# TransmisorVideo5_8GHz.net
KiCad netlist of a schematic drawn in Altium Designer
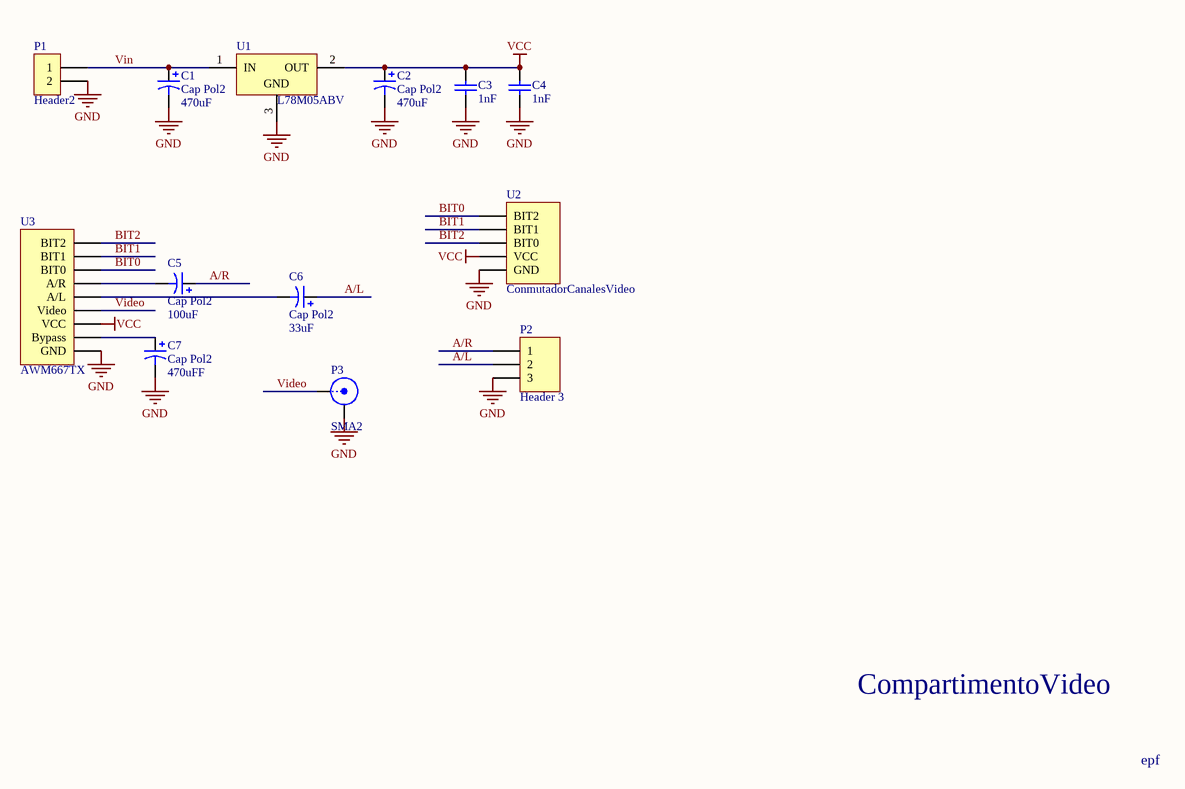
[diagram p0: TransmisorVideo5_8GHz.SchDoc]

(export (version "E")
  (design (tool "Eeschema 10.0.6"))
  (components
    (comp (ref "C1")
      (value "Cap Pol2")
      (footprint "TC7360-2924")
      (description "Polarized Capacitor (Axial)")
      (fields (field (name "ALTIUM_VALUE") "470uF") (field (name "PUBLISHER") "Altium Limited"))
      (libsource (lib "epf") (part "Cap Pol2"))
    )
    (comp (ref "C2")
      (value "Cap Pol2")
      (footprint "TC7360-2924")
      (description "Polarized Capacitor (Axial)")
      (fields (field (name "ALTIUM_VALUE") "470uF") (field (name "PUBLISHER") "Altium Limited"))
      (libsource (lib "epf") (part "Cap Pol2"))
    )
    (comp (ref "C3")
      (value "1nF")
      (footprint "0805_CAP")
      (fields (field (name "Comment") "Capacitor"))
      (libsource (lib "epf") (part "Cap"))
    )
    (comp (ref "C4")
      (value "1nF")
      (footprint "0805_CAP")
      (fields (field (name "Comment") "Capacitor"))
      (libsource (lib "epf") (part "Cap"))
    )
    (comp (ref "C5")
      (value "Cap Pol2")
      (footprint "TC7360-2924")
      (description "Polarized Capacitor (Axial)")
      (fields (field (name "ALTIUM_VALUE") "100uF") (field (name "PUBLISHER") "Altium Limited"))
      (libsource (lib "epf") (part "Cap Pol2"))
    )
    (comp (ref "C6")
      (value "Cap Pol2")
      (footprint "TC7360-2924")
      (description "Polarized Capacitor (Axial)")
      (fields (field (name "ALTIUM_VALUE") "33uF") (field (name "PUBLISHER") "Altium Limited"))
      (libsource (lib "epf") (part "Cap Pol2"))
    )
    (comp (ref "C7")
      (value "Cap Pol2")
      (footprint "TC7360-2924")
      (description "Polarized Capacitor (Axial)")
      (fields (field (name "ALTIUM_VALUE") "470uFF") (field (name "PUBLISHER") "Altium Limited"))
      (libsource (lib "epf") (part "Cap Pol2"))
    )
    (comp (ref "P1") (value "Header2") (footprint "Header2Macho") (libsource (lib "epf") (part "Header2")))
    (comp (ref "P2")
      (value "Header 3")
      (footprint "HDR1X3")
      (description "Header, 3-Pin")
      (fields (field (name "PUBLISHER") "Altium Limited"))
      (libsource (lib "Miscellaneous Connectors") (part "Header 3"))
    )
    (comp (ref "P3")
      (value "SMA2")
      (footprint "SMA-4HOLE")
      (description "BNC Elbow Connector")
      (fields (field (name "PUBLISHER") "Altium Limited"))
      (libsource (lib "epf") (part "SMA2"))
    )
    (comp (ref "U1")
      (value "L78M05ABV")
      (footprint "TO220V")
      (description "Precision 500mA Regulator")
      (fields (field (name "PUBLISHER") "Altium Limited"))
      (libsource (lib "epf") (part "L78M05ABV"))
    )
    (comp (ref "U2")
      (value "ConmutadorCanalesVideo")
      (footprint "Header 3x3")
      (libsource (lib "epf") (part "ConmutadorCanalesVideo"))
    )
    (comp (ref "U3") (value "AWM667TX") (footprint "AWM667TX") (libsource (lib "epf") (part "AWM667TX")))
  )
  (nets
    (net (code "1") (name "/A{slash}L") (class "Default")
      (node (ref "C6") (pin "1") (pinfunction "1_1") (pintype "passive"))
      (node (ref "P2") (pin "2") (pinfunction "2_2") (pintype "passive"))
    )
    (net (code "2") (name "/A{slash}R") (class "Default")
      (node (ref "C5") (pin "1") (pinfunction "1_1") (pintype "passive"))
      (node (ref "P2") (pin "1") (pinfunction "1_1") (pintype "passive"))
    )
    (net (code "3") (name "/BIT0") (class "Default")
      (node (ref "U2") (pin "1") (pinfunction "BIT2_1") (pintype "passive"))
      (node (ref "U3") (pin "3") (pinfunction "BIT0_3") (pintype "passive"))
    )
    (net (code "4") (name "/BIT1") (class "Default")
      (node (ref "U2") (pin "2") (pinfunction "BIT1_2") (pintype "passive"))
      (node (ref "U3") (pin "2") (pinfunction "BIT1_2") (pintype "passive"))
    )
    (net (code "5") (name "/BIT2") (class "Default")
      (node (ref "U2") (pin "3") (pinfunction "BIT0_3") (pintype "passive"))
      (node (ref "U3") (pin "1") (pinfunction "BIT2_1") (pintype "passive"))
    )
    (net (code "6") (name "/Video") (class "Default")
      (node (ref "P3") (pin "1") (pinfunction "X_1") (pintype "passive"))
      (node (ref "U3") (pin "6") (pinfunction "Video_6") (pintype "passive"))
    )
    (net (code "7") (name "/Vin") (class "Default")
      (node (ref "C1") (pin "1") (pinfunction "1_1") (pintype "passive"))
      (node (ref "P1") (pin "1") (pinfunction "1_1") (pintype "passive"))
      (node (ref "U1") (pin "1") (pinfunction "IN_1") (pintype "power_in"))
    )
    (net (code "8") (name "GND") (class "Default")
      (node (ref "C1") (pin "2") (pinfunction "2_2") (pintype "passive"))
      (node (ref "C2") (pin "2") (pinfunction "2_2") (pintype "passive"))
      (node (ref "C3") (pin "1") (pinfunction "1_1") (pintype "passive"))
      (node (ref "C4") (pin "1") (pinfunction "1_1") (pintype "passive"))
      (node (ref "C7") (pin "2") (pinfunction "2_2") (pintype "passive"))
      (node (ref "P1") (pin "2") (pinfunction "2_2") (pintype "passive"))
      (node (ref "P2") (pin "3") (pinfunction "3_3") (pintype "passive"))
      (node (ref "P3") (pin "0") (pinfunction "Y_0") (pintype "passive"))
      (node (ref "U1") (pin "3") (pinfunction "GND_3") (pintype "power_in"))
      (node (ref "U2") (pin "5") (pinfunction "GND_5") (pintype "passive"))
      (node (ref "U3") (pin "9") (pinfunction "GND_9") (pintype "passive"))
    )
    (net (code "9") (name "Net-(U3-A{slash}L)") (class "Default")
      (node (ref "C6") (pin "2") (pinfunction "2_2") (pintype "passive"))
      (node (ref "U3") (pin "5") (pinfunction "A/L_5") (pintype "passive"))
    )
    (net (code "10") (name "Net-(U3-A{slash}R)") (class "Default")
      (node (ref "C5") (pin "2") (pinfunction "2_2") (pintype "passive"))
      (node (ref "U3") (pin "4") (pinfunction "A/R_4") (pintype "passive"))
    )
    (net (code "11") (name "Net-(U3-Bypass)") (class "Default")
      (node (ref "C7") (pin "1") (pinfunction "1_1") (pintype "passive"))
      (node (ref "U3") (pin "8") (pinfunction "Bypass_8") (pintype "passive"))
    )
    (net (code "12") (name "VCC") (class "Default")
      (node (ref "C2") (pin "1") (pinfunction "1_1") (pintype "passive"))
      (node (ref "C3") (pin "2") (pinfunction "2_2") (pintype "passive"))
      (node (ref "C4") (pin "2") (pinfunction "2_2") (pintype "passive"))
      (node (ref "U1") (pin "2") (pinfunction "OUT_2") (pintype "power_in"))
      (node (ref "U2") (pin "4") (pinfunction "VCC_4") (pintype "passive"))
      (node (ref "U3") (pin "7") (pinfunction "VCC_7") (pintype "passive"))
    )
  )
)
